# Sheet1.net
KiCad netlist of a schematic drawn in Altium Designer
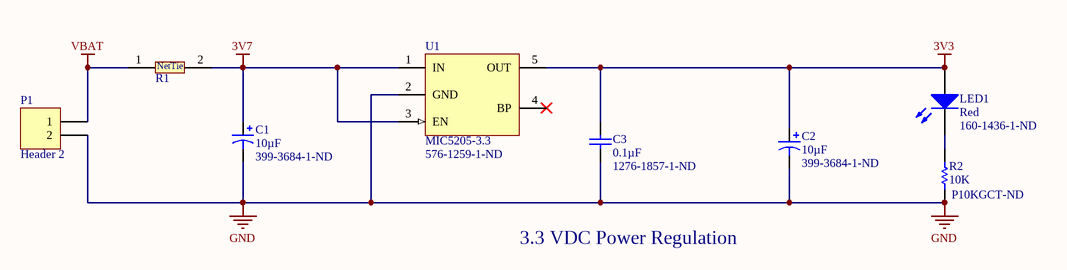
[diagram p0: Sheet1.SchDoc]

(export (version "E")
  (design (tool "Eeschema 10.0.6"))
  (components
    (comp (ref "C1")
      (value "10µF")
      (footprint "CAPC3216_L")
      (description "CAP TANT 10UF 10V 10% 1206")
      (fields
        (field (name "MANUFACTURER") "Kemet")
        (field (name "TOLERANCE") "±10%")
        (field (name "SUPPLIER PART NUMBER 1") "399-3684-1-ND")
      )
      (libsource (lib "Rigid_Flex_Example") (part "CAP_10uF"))
    )
    (comp (ref "C2")
      (value "10µF")
      (footprint "CAPC3216_L")
      (description "CAP TANT 10UF 10V 10% 1206")
      (fields
        (field (name "MANUFACTURER") "Kemet")
        (field (name "TOLERANCE") "±10%")
        (field (name "SUPPLIER PART NUMBER 1") "399-3684-1-ND")
      )
      (libsource (lib "Rigid_Flex_Example") (part "CAP_10uF"))
    )
    (comp (ref "C3")
      (value "0.1µF")
      (footprint "CAPC0603_L")
      (description "CAP CER 0.1UF 25V 10% X5R 0603")
      (fields
        (field (name "TOLERANCE") "±10%")
        (field (name "MANUFACTURER") "Samsung Electro-Mechanics America, Inc")
        (field (name "SUPPLIER PART NUMBER 1") "1276-1857-1-ND")
      )
      (libsource (lib "Rigid_Flex_Example") (part "CAP_100nF"))
    )
    (comp (ref "LED1")
      (value "Red")
      (footprint "0603_A")
      (description "SMD mono-color Chip LED, Red")
      (fields
        (field (name "MANUFACTURER") "Lite-On Inc")
        (field (name "MANUFACTURER PART NUMBER") "LTST-C190KRKT")
        (field (name "SUPPLIER PART NUMBER 1") "160-1436-1-ND")
      )
      (libsource (lib "Rigid_Flex_Example") (part "LED_RED_0603"))
    )
    (comp (ref "P1")
      (value "Header 2")
      (footprint "HDR1X2")
      (description "Header, 2-Pin")
      (fields (field (name "PUBLISHER") "Altium Limited"))
      (libsource (lib "Miscellaneous Connectors") (part "Header 2"))
    )
    (comp (ref "R1")
      (value "NetTie")
      (footprint "NetTie")
      (description "Used to bridge two uniquely named Nets together")
      (libsource (lib "PCB_Project1") (part "NetTie"))
    )
    (comp (ref "R2")
      (value "10K")
      (footprint "RESC0603_L")
      (description "RES SMD 10K OHM 5% 1/10W 0603")
      (fields
        (field (name "TOLERANCE") "5 %")
        (field (name "POWER") "0.1 W")
        (field (name "SUPPLIER PART NUMBER 1") "P10KGCT-ND")
      )
      (libsource (lib "Rigid_Flex_Example") (part "RES_10K"))
    )
    (comp (ref "U1")
      (value "MIC5205-3.3")
      (footprint "SOT-23-OT5_L")
      (description "Voltage Regulator 3.3V")
      (fields
        (field (name "SUPPLIER PART NUMBER 1") "576-1259-1-ND")
        (field (name "MANUFACTURER") "Microchip Technology")
        (field (name "MANUFACTURER PART NUMBER") "MIC5205-3.3YM5-TR")
      )
      (libsource (lib "Rigid_Flex_Example") (part "MIC5205"))
    )
  )
  (nets
    (net (code "1") (name "3V3") (class "Default")
      (node (ref "C2") (pin "1") (pinfunction "1_1") (pintype "passive"))
      (node (ref "C3") (pin "2") (pinfunction "2_2") (pintype "passive"))
      (node (ref "LED1") (pin "2") (pinfunction "A_2") (pintype "passive"))
      (node (ref "U1") (pin "5") (pinfunction "OUT_5") (pintype "power_in"))
    )
    (net (code "2") (name "3V7") (class "Default")
      (node (ref "C1") (pin "1") (pinfunction "1_1") (pintype "passive"))
      (node (ref "R1") (pin "2") (pinfunction "2_2") (pintype "passive"))
      (node (ref "U1") (pin "1") (pinfunction "IN_1") (pintype "power_in"))
      (node (ref "U1") (pin "3") (pinfunction "EN_3") (pintype "input"))
    )
    (net (code "3") (name "GND") (class "Default")
      (node (ref "C1") (pin "2") (pinfunction "2_2") (pintype "passive"))
      (node (ref "C2") (pin "2") (pinfunction "2_2") (pintype "passive"))
      (node (ref "C3") (pin "1") (pinfunction "1_1") (pintype "passive"))
      (node (ref "P1") (pin "2") (pinfunction "2_2") (pintype "passive"))
      (node (ref "R2") (pin "1") (pinfunction "1_1") (pintype "passive"))
      (node (ref "U1") (pin "2") (pinfunction "GND_2") (pintype "power_in"))
    )
    (net (code "4") (name "Net-(LED1-K)") (class "Default")
      (node (ref "LED1") (pin "1") (pinfunction "K_1") (pintype "passive"))
      (node (ref "R2") (pin "2") (pinfunction "2_2") (pintype "passive"))
    )
    (net (code "5") (name "VBAT") (class "Default")
      (node (ref "P1") (pin "1") (pinfunction "1_1") (pintype "passive"))
      (node (ref "R1") (pin "1") (pinfunction "1_1") (pintype "passive"))
    )
    (net (code "6") (name "unconnected-(U1-BP-Pad4)") (class "Default")
      (node (ref "U1") (pin "4") (pinfunction "BP_4") (pintype "power_in+no_connect"))
    )
  )
)
